# smoothieboard-alt-p3.net
KiCad netlist of a schematic drawn in Altium Designer
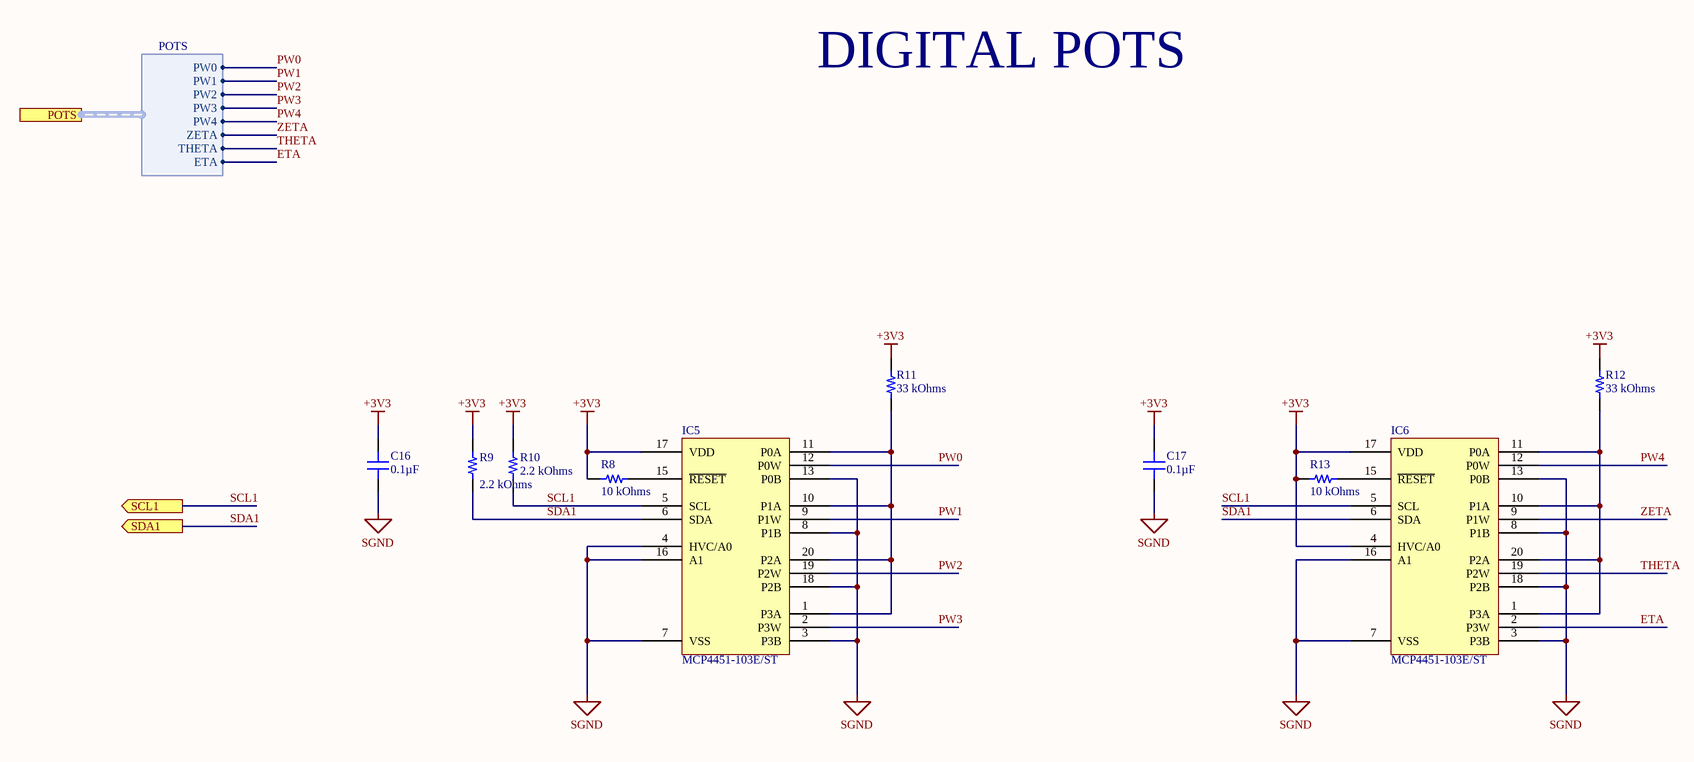
[diagram p0: smoothieboard-alt-p3.SchDoc]

(export (version "E")
  (design (tool "Eeschema 10.0.6"))
  (components
    (comp (ref "C16")
      (value "0.1µF")
      (footprint "CAP 0402_1005")
      (description "CAP CER 0.1UF 6.3V X5R 0402")
      (fields (field (name "PART NUMBER") "CC0402MRX5R5BB104") (field (name "MANUFACTURER") "Yageo"))
      (libsource (lib "CAL") (part "Capacitor"))
    )
    (comp (ref "C17")
      (value "0.1µF")
      (footprint "CAP 0402_1005")
      (description "CAP CER 0.1UF 6.3V X5R 0402")
      (fields (field (name "PART NUMBER") "CC0402MRX5R5BB104") (field (name "MANUFACTURER") "Yageo"))
      (libsource (lib "CAL") (part "Capacitor"))
    )
    (comp (ref "IC5")
      (value "MCP4451-103E/ST")
      (footprint "MICROCHIP TSSOP-20 4.4MM BODY")
      (description "IC DGT POT 10KOHM 257TAP 20TSSOP")
      (fields (field (name "MANUFACTURER") "Microchip Technology") (field (name "TOLERANCE") "±20%"))
      (libsource (lib "CAL") (part "MICROCHIP MCP44x1 POT TSSOP"))
    )
    (comp (ref "IC6")
      (value "MCP4451-103E/ST")
      (footprint "MICROCHIP TSSOP-20 4.4MM BODY")
      (description "IC DGT POT 10KOHM 257TAP 20TSSOP")
      (fields (field (name "MANUFACTURER") "Microchip Technology") (field (name "TOLERANCE") "±20%"))
      (libsource (lib "CAL") (part "MICROCHIP MCP44x1 POT TSSOP"))
    )
    (comp (ref "R8")
      (value "10 kOhms")
      (footprint "RES 0402_1005")
      (description "RES SMD 10K OHM 5% 1/16W 0402")
      (fields (field (name "PART NUMBER") "CRCW040210K0JNTD") (field (name "MANUFACTURER") "Vishay Dale"))
      (libsource (lib "CAL") (part "Resistor"))
    )
    (comp (ref "R9")
      (value "2.2 kOhms")
      (footprint "RES 0402_1005")
      (description "RES SMD 0402 1/5W 1% 2.2K OHM")
      (fields (field (name "PART NUMBER") "SR0402FR-7T2K2L") (field (name "MANUFACTURER") "Yageo"))
      (libsource (lib "CAL") (part "Resistor"))
    )
    (comp (ref "R10")
      (value "2.2 kOhms")
      (footprint "RES 0402_1005")
      (description "RES SMD 0402 1/5W 1% 2.2K OHM")
      (fields (field (name "PART NUMBER") "SR0402FR-7T2K2L") (field (name "MANUFACTURER") "Yageo"))
      (libsource (lib "CAL") (part "Resistor"))
    )
    (comp (ref "R11")
      (value "33 kOhms")
      (footprint "RES 0402_1005")
      (description "RES SMD 33K OHM 1% 1/16W 0402")
      (fields (field (name "PART NUMBER") "RT0402FRE0733KL") (field (name "MANUFACTURER") "Yageo"))
      (libsource (lib "CAL") (part "Resistor"))
    )
    (comp (ref "R12")
      (value "33 kOhms")
      (footprint "RES 0402_1005")
      (description "RES SMD 33K OHM 1% 1/16W 0402")
      (fields (field (name "PART NUMBER") "RT0402FRE0733KL") (field (name "MANUFACTURER") "Yageo"))
      (libsource (lib "CAL") (part "Resistor"))
    )
    (comp (ref "R13")
      (value "10 kOhms")
      (footprint "RES 0402_1005")
      (description "RES SMD 10K OHM 5% 1/16W 0402")
      (fields (field (name "PART NUMBER") "CRCW040210K0JNTD") (field (name "MANUFACTURER") "Vishay Dale"))
      (libsource (lib "CAL") (part "Resistor"))
    )
  )
  (nets
    (net (code "2") (name "+3V3") (class "Default")
      (node (ref "C16") (pin "2") (pinfunction "2_2") (pintype "passive"))
      (node (ref "C17") (pin "2") (pinfunction "2_2") (pintype "passive"))
      (node (ref "IC5") (pin "17") (pinfunction "VDD_17") (pintype "passive"))
      (node (ref "IC6") (pin "17") (pinfunction "VDD_17") (pintype "passive"))
      (node (ref "IC6") (pin "4") (pinfunction "HVC/A0_4") (pintype "passive"))
      (node (ref "R10") (pin "2") (pinfunction "2_2") (pintype "passive"))
      (node (ref "R11") (pin "2") (pinfunction "2_2") (pintype "passive"))
      (node (ref "R12") (pin "2") (pinfunction "2_2") (pintype "passive"))
      (node (ref "R13") (pin "2") (pinfunction "2_2") (pintype "passive"))
      (node (ref "R8") (pin "2") (pinfunction "2_2") (pintype "passive"))
      (node (ref "R9") (pin "2") (pinfunction "2_2") (pintype "passive"))
    )
    (net (code "3") (name "/ETA") (class "Default")
      (node (ref "IC6") (pin "2") (pinfunction "P3W_2") (pintype "passive"))
    )
    (net (code "4") (name "/PW0") (class "Default")
      (node (ref "IC5") (pin "12") (pinfunction "P0W_12") (pintype "passive"))
    )
    (net (code "5") (name "/PW1") (class "Default")
      (node (ref "IC5") (pin "9") (pinfunction "P1W_9") (pintype "passive"))
    )
    (net (code "6") (name "/PW2") (class "Default")
      (node (ref "IC5") (pin "19") (pinfunction "P2W_19") (pintype "passive"))
    )
    (net (code "7") (name "/PW3") (class "Default")
      (node (ref "IC5") (pin "2") (pinfunction "P3W_2") (pintype "passive"))
    )
    (net (code "8") (name "/PW4") (class "Default")
      (node (ref "IC6") (pin "12") (pinfunction "P0W_12") (pintype "passive"))
    )
    (net (code "9") (name "/SCL1") (class "Default")
      (node (ref "IC5") (pin "5") (pinfunction "SCL_5") (pintype "passive"))
      (node (ref "IC6") (pin "5") (pinfunction "SCL_5") (pintype "passive"))
      (node (ref "R10") (pin "1") (pinfunction "1_1") (pintype "passive"))
    )
    (net (code "10") (name "/SDA1") (class "Default")
      (node (ref "IC5") (pin "6") (pinfunction "SDA_6") (pintype "passive"))
      (node (ref "IC6") (pin "6") (pinfunction "SDA_6") (pintype "passive"))
      (node (ref "R9") (pin "1") (pinfunction "1_1") (pintype "passive"))
    )
    (net (code "11") (name "/THETA") (class "Default")
      (node (ref "IC6") (pin "19") (pinfunction "P2W_19") (pintype "passive"))
    )
    (net (code "12") (name "/ZETA") (class "Default")
      (node (ref "IC6") (pin "9") (pinfunction "P1W_9") (pintype "passive"))
    )
    (net (code "14") (name "Net-(IC5-P0A)") (class "Default")
      (node (ref "IC5") (pin "1") (pinfunction "P3A_1") (pintype "passive"))
      (node (ref "IC5") (pin "10") (pinfunction "P1A_10") (pintype "passive"))
      (node (ref "IC5") (pin "11") (pinfunction "P0A_11") (pintype "passive"))
      (node (ref "IC5") (pin "20") (pinfunction "P2A_20") (pintype "passive"))
      (node (ref "R11") (pin "1") (pinfunction "1_1") (pintype "passive"))
    )
    (net (code "15") (name "Net-(IC5-~{RESET})") (class "Default")
      (node (ref "IC5") (pin "15") (pinfunction "~{RESET}_15") (pintype "passive"))
      (node (ref "R8") (pin "1") (pinfunction "1_1") (pintype "passive"))
    )
    (net (code "16") (name "Net-(IC6-P0A)") (class "Default")
      (node (ref "IC6") (pin "1") (pinfunction "P3A_1") (pintype "passive"))
      (node (ref "IC6") (pin "10") (pinfunction "P1A_10") (pintype "passive"))
      (node (ref "IC6") (pin "11") (pinfunction "P0A_11") (pintype "passive"))
      (node (ref "IC6") (pin "20") (pinfunction "P2A_20") (pintype "passive"))
      (node (ref "R12") (pin "1") (pinfunction "1_1") (pintype "passive"))
    )
    (net (code "17") (name "Net-(IC6-~{RESET})") (class "Default")
      (node (ref "IC6") (pin "15") (pinfunction "~{RESET}_15") (pintype "passive"))
      (node (ref "R13") (pin "1") (pinfunction "1_1") (pintype "passive"))
    )
    (net (code "18") (name "SGND") (class "Default")
      (node (ref "C16") (pin "1") (pinfunction "1_1") (pintype "passive"))
      (node (ref "C17") (pin "1") (pinfunction "1_1") (pintype "passive"))
      (node (ref "IC5") (pin "13") (pinfunction "P0B_13") (pintype "passive"))
      (node (ref "IC5") (pin "16") (pinfunction "A1_16") (pintype "passive"))
      (node (ref "IC5") (pin "18") (pinfunction "P2B_18") (pintype "passive"))
      (node (ref "IC5") (pin "3") (pinfunction "P3B_3") (pintype "passive"))
      (node (ref "IC5") (pin "4") (pinfunction "HVC/A0_4") (pintype "passive"))
      (node (ref "IC5") (pin "7") (pinfunction "VSS_7") (pintype "passive"))
      (node (ref "IC5") (pin "8") (pinfunction "P1B_8") (pintype "passive"))
      (node (ref "IC6") (pin "13") (pinfunction "P0B_13") (pintype "passive"))
      (node (ref "IC6") (pin "16") (pinfunction "A1_16") (pintype "passive"))
      (node (ref "IC6") (pin "18") (pinfunction "P2B_18") (pintype "passive"))
      (node (ref "IC6") (pin "3") (pinfunction "P3B_3") (pintype "passive"))
      (node (ref "IC6") (pin "7") (pinfunction "VSS_7") (pintype "passive"))
      (node (ref "IC6") (pin "8") (pinfunction "P1B_8") (pintype "passive"))
    )
  )
)
